# main.net
KiCad netlist of a schematic drawn in EAGLE
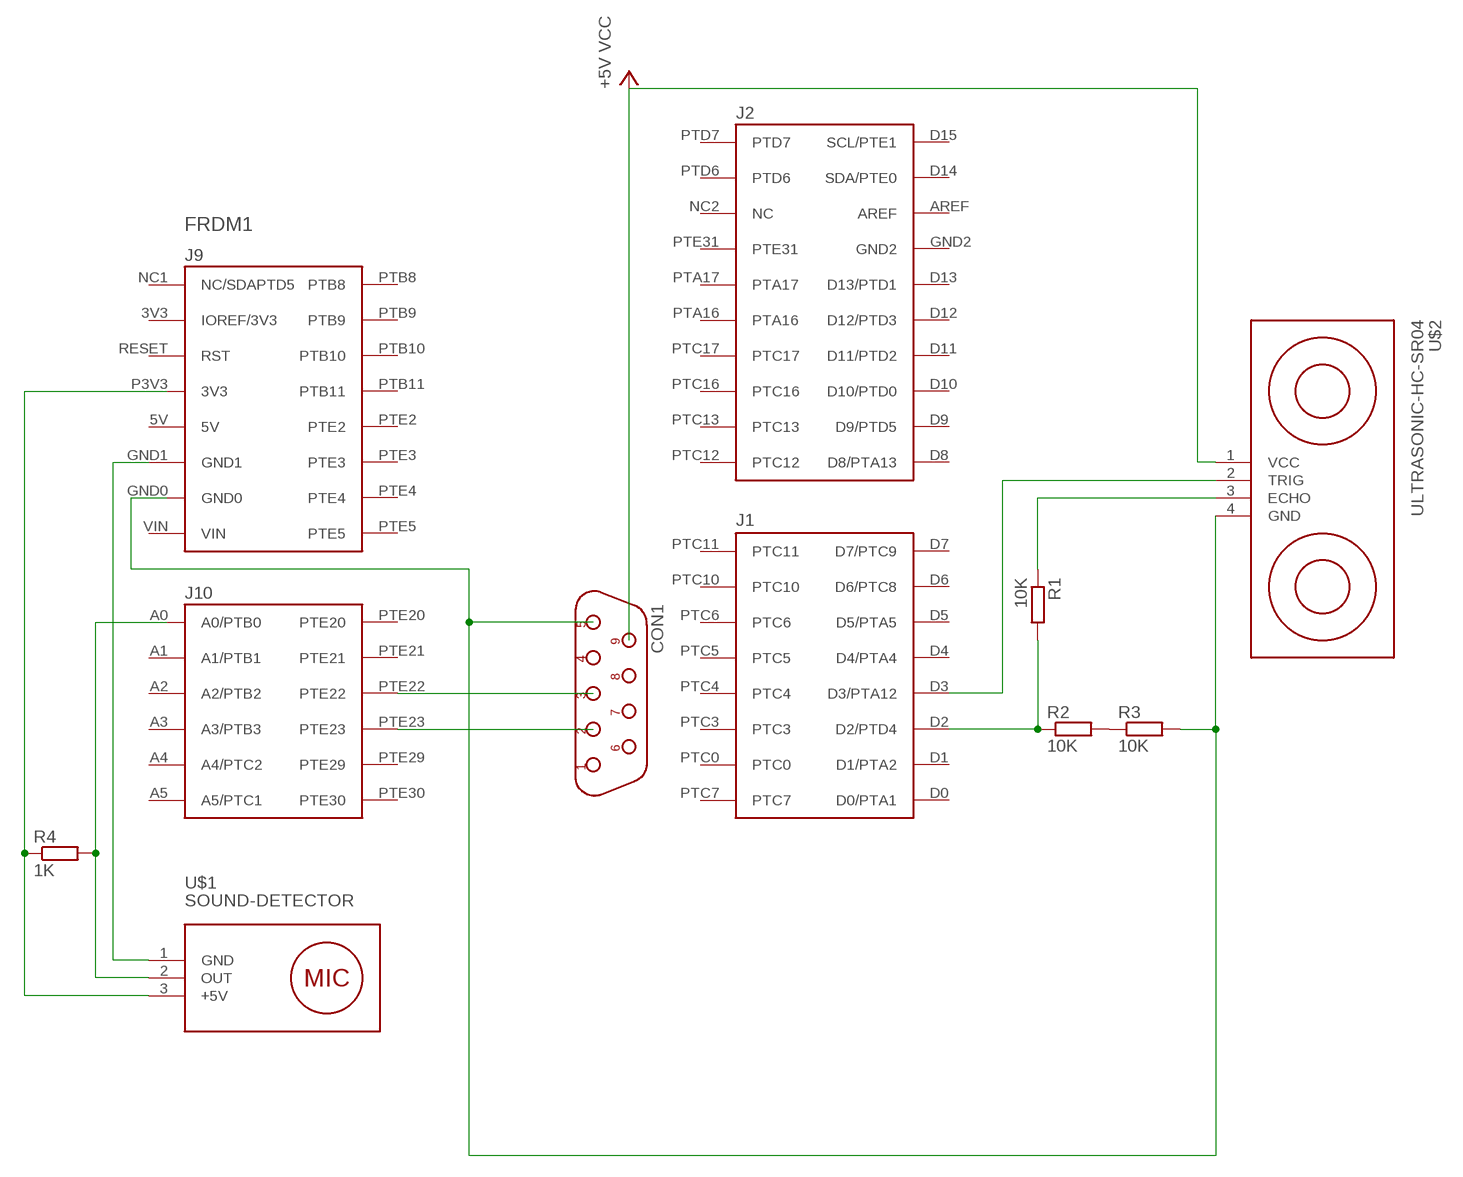
[diagram p0: schematic, sheet 1]

(export (version "E")
  (design (tool "Eeschema 10.0.6"))
  (components
    (comp (ref "CON1")
      (value "DB9F")
      (footprint "eagle-import:D-09F")
      (libsource (lib "eagle-import") (part "DB9F"))
    )
    (comp (ref "FRDM1")
      (value "FRDM-KL25ZNORMAL")
      (footprint "eagle-import:FRDM_KL25Z_NORMAL")
      (libsource (lib "eagle-import") (part "FRDM-KL25ZNORMAL"))
    )
    (comp (ref "R1")
      (value "10K")
      (footprint "eagle-import:0204_7")
      (libsource (lib "eagle-import") (part "R-EU_0204/7"))
    )
    (comp (ref "R2")
      (value "10K")
      (footprint "eagle-import:0204_7")
      (libsource (lib "eagle-import") (part "R-EU_0204/7"))
    )
    (comp (ref "R3")
      (value "10K")
      (footprint "eagle-import:0204_7")
      (libsource (lib "eagle-import") (part "R-EU_0204/7"))
    )
    (comp (ref "R4")
      (value "1K")
      (footprint "eagle-import:0204_7")
      (libsource (lib "eagle-import") (part "R-EU_0204/7"))
    )
    (comp (ref "U$1")
      (value "SOUND-DETECTOR")
      (footprint "eagle-import:SOUND-DETECTOR")
      (libsource (lib "eagle-import") (part "SOUND-DETECTOR"))
    )
    (comp (ref "U$2")
      (value "ULTRASONIC-HC-SR04")
      (footprint "eagle-import:ULTRASONIC-HC-SR04")
      (libsource (lib "eagle-import") (part "ULTRASONIC-HC-SR04"))
    )
  )
  (nets
    (net (code "1") (name "+5V VCC") (class "Default")
      (node (ref "CON1") (pin "9") (pinfunction "9_9") (pintype "passive"))
      (node (ref "U$2") (pin "1") (pinfunction "VCC_1") (pintype "power_in"))
    )
    (net (code "2") (name "Net-(CON1-Pad2)") (class "Default")
      (node (ref "CON1") (pin "2") (pinfunction "2_2") (pintype "passive"))
      (node (ref "FRDM1") (pin "PTE23") (pinfunction "PTE23_PTE23") (pintype "bidirectional"))
    )
    (net (code "3") (name "Net-(CON1-Pad3)") (class "Default")
      (node (ref "CON1") (pin "3") (pinfunction "3_3") (pintype "passive"))
      (node (ref "FRDM1") (pin "PTE22") (pinfunction "PTE22_PTE22") (pintype "bidirectional"))
    )
    (net (code "4") (name "Net-(FRDM1-D2{slash}PTD4)") (class "Default")
      (node (ref "FRDM1") (pin "D2") (pinfunction "D2/PTD4_D2") (pintype "bidirectional"))
      (node (ref "R1") (pin "2") (pinfunction "2_2") (pintype "passive"))
      (node (ref "R2") (pin "1") (pinfunction "1_1") (pintype "passive"))
    )
    (net (code "5") (name "Net-(FRDM1-D3{slash}PTA12)") (class "Default")
      (node (ref "FRDM1") (pin "D3") (pinfunction "D3/PTA12_D3") (pintype "bidirectional"))
      (node (ref "U$2") (pin "2") (pinfunction "TRIG_2") (pintype "input"))
    )
    (net (code "6") (name "Net-(R2-Pad2)") (class "Default")
      (node (ref "R2") (pin "2") (pinfunction "2_2") (pintype "passive"))
      (node (ref "R3") (pin "1") (pinfunction "1_1") (pintype "passive"))
    )
    (net (code "7") (name "Net-(U$1-+5V)") (class "Default")
      (node (ref "R4") (pin "1") (pinfunction "1_1") (pintype "passive"))
      (node (ref "U$1") (pin "3") (pinfunction "+5V_3") (pintype "power_in"))
    )
    (net (code "8") (name "Net-(U$1-GND)") (class "Default")
      (node (ref "FRDM1") (pin "GND1") (pinfunction "GND1_GND1") (pintype "bidirectional"))
      (node (ref "U$1") (pin "1") (pinfunction "GND_1") (pintype "power_in"))
    )
    (net (code "9") (name "Net-(U$1-OUT)") (class "Default")
      (node (ref "R4") (pin "2") (pinfunction "2_2") (pintype "passive"))
      (node (ref "U$1") (pin "2") (pinfunction "OUT_2") (pintype "output"))
    )
    (net (code "10") (name "Net-(U$2-ECHO)") (class "Default")
      (node (ref "R1") (pin "1") (pinfunction "1_1") (pintype "passive"))
      (node (ref "U$2") (pin "3") (pinfunction "ECHO_3") (pintype "output"))
    )
    (net (code "11") (name "Net-(U$2-GND)") (class "Default")
      (node (ref "CON1") (pin "5") (pinfunction "5_5") (pintype "passive"))
      (node (ref "R3") (pin "2") (pinfunction "2_2") (pintype "passive"))
      (node (ref "U$2") (pin "4") (pinfunction "GND_4") (pintype "power_in"))
    )
    (net (code "12") (name "unconnected-(CON1-Pad1)") (class "Default")
      (node (ref "CON1") (pin "1") (pinfunction "1_1") (pintype "passive"))
    )
    (net (code "13") (name "unconnected-(CON1-Pad4)") (class "Default")
      (node (ref "CON1") (pin "4") (pinfunction "4_4") (pintype "passive"))
    )
    (net (code "14") (name "unconnected-(CON1-Pad6)") (class "Default")
      (node (ref "CON1") (pin "6") (pinfunction "6_6") (pintype "passive"))
    )
    (net (code "15") (name "unconnected-(CON1-Pad7)") (class "Default")
      (node (ref "CON1") (pin "7") (pinfunction "7_7") (pintype "passive"))
    )
    (net (code "16") (name "unconnected-(CON1-Pad8)") (class "Default")
      (node (ref "CON1") (pin "8") (pinfunction "8_8") (pintype "passive"))
    )
    (net (code "17") (name "unconnected-(FRDM1-3V3-PadP3V3)") (class "Default")
      (node (ref "FRDM1") (pin "P3V3") (pinfunction "3V3_P3V3") (pintype "bidirectional"))
    )
    (net (code "18") (name "unconnected-(FRDM1-A0{slash}PTB0-PadA0)") (class "Default")
      (node (ref "FRDM1") (pin "A0") (pinfunction "A0/PTB0_A0") (pintype "bidirectional"))
    )
    (net (code "19") (name "unconnected-(FRDM1-A1{slash}PTB1-PadA1)") (class "Default")
      (node (ref "FRDM1") (pin "A1") (pinfunction "A1/PTB1_A1") (pintype "bidirectional"))
    )
    (net (code "20") (name "unconnected-(FRDM1-A2{slash}PTB2-PadA2)") (class "Default")
      (node (ref "FRDM1") (pin "A2") (pinfunction "A2/PTB2_A2") (pintype "bidirectional"))
    )
    (net (code "21") (name "unconnected-(FRDM1-A3{slash}PTB3-PadA3)") (class "Default")
      (node (ref "FRDM1") (pin "A3") (pinfunction "A3/PTB3_A3") (pintype "bidirectional"))
    )
    (net (code "22") (name "unconnected-(FRDM1-A4{slash}PTC2-PadA4)") (class "Default")
      (node (ref "FRDM1") (pin "A4") (pinfunction "A4/PTC2_A4") (pintype "bidirectional"))
    )
    (net (code "23") (name "unconnected-(FRDM1-A5{slash}PTC1-PadA5)") (class "Default")
      (node (ref "FRDM1") (pin "A5") (pinfunction "A5/PTC1_A5") (pintype "bidirectional"))
    )
    (net (code "24") (name "unconnected-(FRDM1-D0{slash}PTA1-PadD0)") (class "Default")
      (node (ref "FRDM1") (pin "D0") (pinfunction "D0/PTA1_D0") (pintype "bidirectional"))
    )
    (net (code "25") (name "unconnected-(FRDM1-D1{slash}PTA2-PadD1)") (class "Default")
      (node (ref "FRDM1") (pin "D1") (pinfunction "D1/PTA2_D1") (pintype "bidirectional"))
    )
    (net (code "26") (name "unconnected-(FRDM1-D4{slash}PTA4-PadD4)") (class "Default")
      (node (ref "FRDM1") (pin "D4") (pinfunction "D4/PTA4_D4") (pintype "bidirectional"))
    )
    (net (code "27") (name "unconnected-(FRDM1-D5{slash}PTA5-PadD5)") (class "Default")
      (node (ref "FRDM1") (pin "D5") (pinfunction "D5/PTA5_D5") (pintype "bidirectional"))
    )
    (net (code "28") (name "unconnected-(FRDM1-D6{slash}PTC8-PadD6)") (class "Default")
      (node (ref "FRDM1") (pin "D6") (pinfunction "D6/PTC8_D6") (pintype "bidirectional"))
    )
    (net (code "29") (name "unconnected-(FRDM1-D7{slash}PTC9-PadD7)") (class "Default")
      (node (ref "FRDM1") (pin "D7") (pinfunction "D7/PTC9_D7") (pintype "bidirectional"))
    )
    (net (code "30") (name "unconnected-(FRDM1-D8{slash}PTA13-PadD8)") (class "Default")
      (node (ref "FRDM1") (pin "D8") (pinfunction "D8/PTA13_D8") (pintype "bidirectional"))
    )
    (net (code "31") (name "unconnected-(FRDM1-D9{slash}PTD5-PadD9)") (class "Default")
      (node (ref "FRDM1") (pin "D9") (pinfunction "D9/PTD5_D9") (pintype "bidirectional"))
    )
    (net (code "32") (name "unconnected-(FRDM1-D10{slash}PTD0-PadD10)") (class "Default")
      (node (ref "FRDM1") (pin "D10") (pinfunction "D10/PTD0_D10") (pintype "bidirectional"))
    )
    (net (code "33") (name "unconnected-(FRDM1-D11{slash}PTD2-PadD11)") (class "Default")
      (node (ref "FRDM1") (pin "D11") (pinfunction "D11/PTD2_D11") (pintype "bidirectional"))
    )
    (net (code "34") (name "unconnected-(FRDM1-D12{slash}PTD3-PadD12)") (class "Default")
      (node (ref "FRDM1") (pin "D12") (pinfunction "D12/PTD3_D12") (pintype "bidirectional"))
    )
    (net (code "35") (name "unconnected-(FRDM1-D13{slash}PTD1-PadD13)") (class "Default")
      (node (ref "FRDM1") (pin "D13") (pinfunction "D13/PTD1_D13") (pintype "bidirectional"))
    )
    (net (code "36") (name "unconnected-(FRDM1-IOREF{slash}3V3-Pad3V3)") (class "Default")
      (node (ref "FRDM1") (pin "3V3") (pinfunction "IOREF/3V3_3V3") (pintype "bidirectional"))
    )
    (net (code "37") (name "unconnected-(FRDM1-NC-PadNC2)") (class "Default")
      (node (ref "FRDM1") (pin "NC2") (pinfunction "NC_NC2") (pintype "bidirectional"))
    )
    (net (code "38") (name "unconnected-(FRDM1-NC{slash}SDAPTD5-PadNC1)") (class "Default")
      (node (ref "FRDM1") (pin "NC1") (pinfunction "NC/SDAPTD5_NC1") (pintype "bidirectional"))
    )
    (net (code "39") (name "unconnected-(FRDM1-Pad5V)") (class "Default")
      (node (ref "FRDM1") (pin "5V") (pinfunction "5V_5V") (pintype "bidirectional"))
    )
    (net (code "40") (name "unconnected-(FRDM1-PadAREF)") (class "Default")
      (node (ref "FRDM1") (pin "AREF") (pinfunction "AREF_AREF") (pintype "bidirectional"))
    )
    (net (code "41") (name "unconnected-(FRDM1-PadGND0)") (class "Default")
      (node (ref "FRDM1") (pin "GND0") (pinfunction "GND0_GND0") (pintype "bidirectional"))
    )
    (net (code "42") (name "unconnected-(FRDM1-PadGND2)") (class "Default")
      (node (ref "FRDM1") (pin "GND2") (pinfunction "GND2_GND2") (pintype "bidirectional"))
    )
    (net (code "43") (name "unconnected-(FRDM1-PadPTA16)") (class "Default")
      (node (ref "FRDM1") (pin "PTA16") (pinfunction "PTA16_PTA16") (pintype "bidirectional"))
    )
    (net (code "44") (name "unconnected-(FRDM1-PadPTA17)") (class "Default")
      (node (ref "FRDM1") (pin "PTA17") (pinfunction "PTA17_PTA17") (pintype "bidirectional"))
    )
    (net (code "45") (name "unconnected-(FRDM1-PadPTB8)") (class "Default")
      (node (ref "FRDM1") (pin "PTB8") (pinfunction "PTB8_PTB8") (pintype "bidirectional"))
    )
    (net (code "46") (name "unconnected-(FRDM1-PadPTB9)") (class "Default")
      (node (ref "FRDM1") (pin "PTB9") (pinfunction "PTB9_PTB9") (pintype "bidirectional"))
    )
    (net (code "47") (name "unconnected-(FRDM1-PadPTB10)") (class "Default")
      (node (ref "FRDM1") (pin "PTB10") (pinfunction "PTB10_PTB10") (pintype "bidirectional"))
    )
    (net (code "48") (name "unconnected-(FRDM1-PadPTB11)") (class "Default")
      (node (ref "FRDM1") (pin "PTB11") (pinfunction "PTB11_PTB11") (pintype "bidirectional"))
    )
    (net (code "49") (name "unconnected-(FRDM1-PadPTC0)") (class "Default")
      (node (ref "FRDM1") (pin "PTC0") (pinfunction "PTC0_PTC0") (pintype "bidirectional"))
    )
    (net (code "50") (name "unconnected-(FRDM1-PadPTC3)") (class "Default")
      (node (ref "FRDM1") (pin "PTC3") (pinfunction "PTC3_PTC3") (pintype "bidirectional"))
    )
    (net (code "51") (name "unconnected-(FRDM1-PadPTC4)") (class "Default")
      (node (ref "FRDM1") (pin "PTC4") (pinfunction "PTC4_PTC4") (pintype "bidirectional"))
    )
    (net (code "52") (name "unconnected-(FRDM1-PadPTC5)") (class "Default")
      (node (ref "FRDM1") (pin "PTC5") (pinfunction "PTC5_PTC5") (pintype "bidirectional"))
    )
    (net (code "53") (name "unconnected-(FRDM1-PadPTC6)") (class "Default")
      (node (ref "FRDM1") (pin "PTC6") (pinfunction "PTC6_PTC6") (pintype "bidirectional"))
    )
    (net (code "54") (name "unconnected-(FRDM1-PadPTC7)") (class "Default")
      (node (ref "FRDM1") (pin "PTC7") (pinfunction "PTC7_PTC7") (pintype "bidirectional"))
    )
    (net (code "55") (name "unconnected-(FRDM1-PadPTC10)") (class "Default")
      (node (ref "FRDM1") (pin "PTC10") (pinfunction "PTC10_PTC10") (pintype "bidirectional"))
    )
    (net (code "56") (name "unconnected-(FRDM1-PadPTC11)") (class "Default")
      (node (ref "FRDM1") (pin "PTC11") (pinfunction "PTC11_PTC11") (pintype "bidirectional"))
    )
    (net (code "57") (name "unconnected-(FRDM1-PadPTC12)") (class "Default")
      (node (ref "FRDM1") (pin "PTC12") (pinfunction "PTC12_PTC12") (pintype "bidirectional"))
    )
    (net (code "58") (name "unconnected-(FRDM1-PadPTC13)") (class "Default")
      (node (ref "FRDM1") (pin "PTC13") (pinfunction "PTC13_PTC13") (pintype "bidirectional"))
    )
    (net (code "59") (name "unconnected-(FRDM1-PadPTC16)") (class "Default")
      (node (ref "FRDM1") (pin "PTC16") (pinfunction "PTC16_PTC16") (pintype "bidirectional"))
    )
    (net (code "60") (name "unconnected-(FRDM1-PadPTC17)") (class "Default")
      (node (ref "FRDM1") (pin "PTC17") (pinfunction "PTC17_PTC17") (pintype "bidirectional"))
    )
    (net (code "61") (name "unconnected-(FRDM1-PadPTD6)") (class "Default")
      (node (ref "FRDM1") (pin "PTD6") (pinfunction "PTD6_PTD6") (pintype "bidirectional"))
    )
    (net (code "62") (name "unconnected-(FRDM1-PadPTD7)") (class "Default")
      (node (ref "FRDM1") (pin "PTD7") (pinfunction "PTD7_PTD7") (pintype "bidirectional"))
    )
    (net (code "63") (name "unconnected-(FRDM1-PadPTE2)") (class "Default")
      (node (ref "FRDM1") (pin "PTE2") (pinfunction "PTE2_PTE2") (pintype "bidirectional"))
    )
    (net (code "64") (name "unconnected-(FRDM1-PadPTE3)") (class "Default")
      (node (ref "FRDM1") (pin "PTE3") (pinfunction "PTE3_PTE3") (pintype "bidirectional"))
    )
    (net (code "65") (name "unconnected-(FRDM1-PadPTE4)") (class "Default")
      (node (ref "FRDM1") (pin "PTE4") (pinfunction "PTE4_PTE4") (pintype "bidirectional"))
    )
    (net (code "66") (name "unconnected-(FRDM1-PadPTE5)") (class "Default")
      (node (ref "FRDM1") (pin "PTE5") (pinfunction "PTE5_PTE5") (pintype "bidirectional"))
    )
    (net (code "67") (name "unconnected-(FRDM1-PadPTE20)") (class "Default")
      (node (ref "FRDM1") (pin "PTE20") (pinfunction "PTE20_PTE20") (pintype "bidirectional"))
    )
    (net (code "68") (name "unconnected-(FRDM1-PadPTE21)") (class "Default")
      (node (ref "FRDM1") (pin "PTE21") (pinfunction "PTE21_PTE21") (pintype "bidirectional"))
    )
    (net (code "69") (name "unconnected-(FRDM1-PadPTE29)") (class "Default")
      (node (ref "FRDM1") (pin "PTE29") (pinfunction "PTE29_PTE29") (pintype "bidirectional"))
    )
    (net (code "70") (name "unconnected-(FRDM1-PadPTE30)") (class "Default")
      (node (ref "FRDM1") (pin "PTE30") (pinfunction "PTE30_PTE30") (pintype "bidirectional"))
    )
    (net (code "71") (name "unconnected-(FRDM1-PadPTE31)") (class "Default")
      (node (ref "FRDM1") (pin "PTE31") (pinfunction "PTE31_PTE31") (pintype "bidirectional"))
    )
    (net (code "72") (name "unconnected-(FRDM1-PadVIN)") (class "Default")
      (node (ref "FRDM1") (pin "VIN") (pinfunction "VIN_VIN") (pintype "bidirectional"))
    )
    (net (code "73") (name "unconnected-(FRDM1-RST-PadRESET)") (class "Default")
      (node (ref "FRDM1") (pin "RESET") (pinfunction "RST_RESET") (pintype "bidirectional"))
    )
    (net (code "74") (name "unconnected-(FRDM1-SCL{slash}PTE1-PadD15)") (class "Default")
      (node (ref "FRDM1") (pin "D15") (pinfunction "SCL/PTE1_D15") (pintype "bidirectional"))
    )
    (net (code "75") (name "unconnected-(FRDM1-SDA{slash}PTE0-PadD14)") (class "Default")
      (node (ref "FRDM1") (pin "D14") (pinfunction "SDA/PTE0_D14") (pintype "bidirectional"))
    )
  )
)
